# ECG.net
KiCad netlist of a schematic drawn in EAGLE
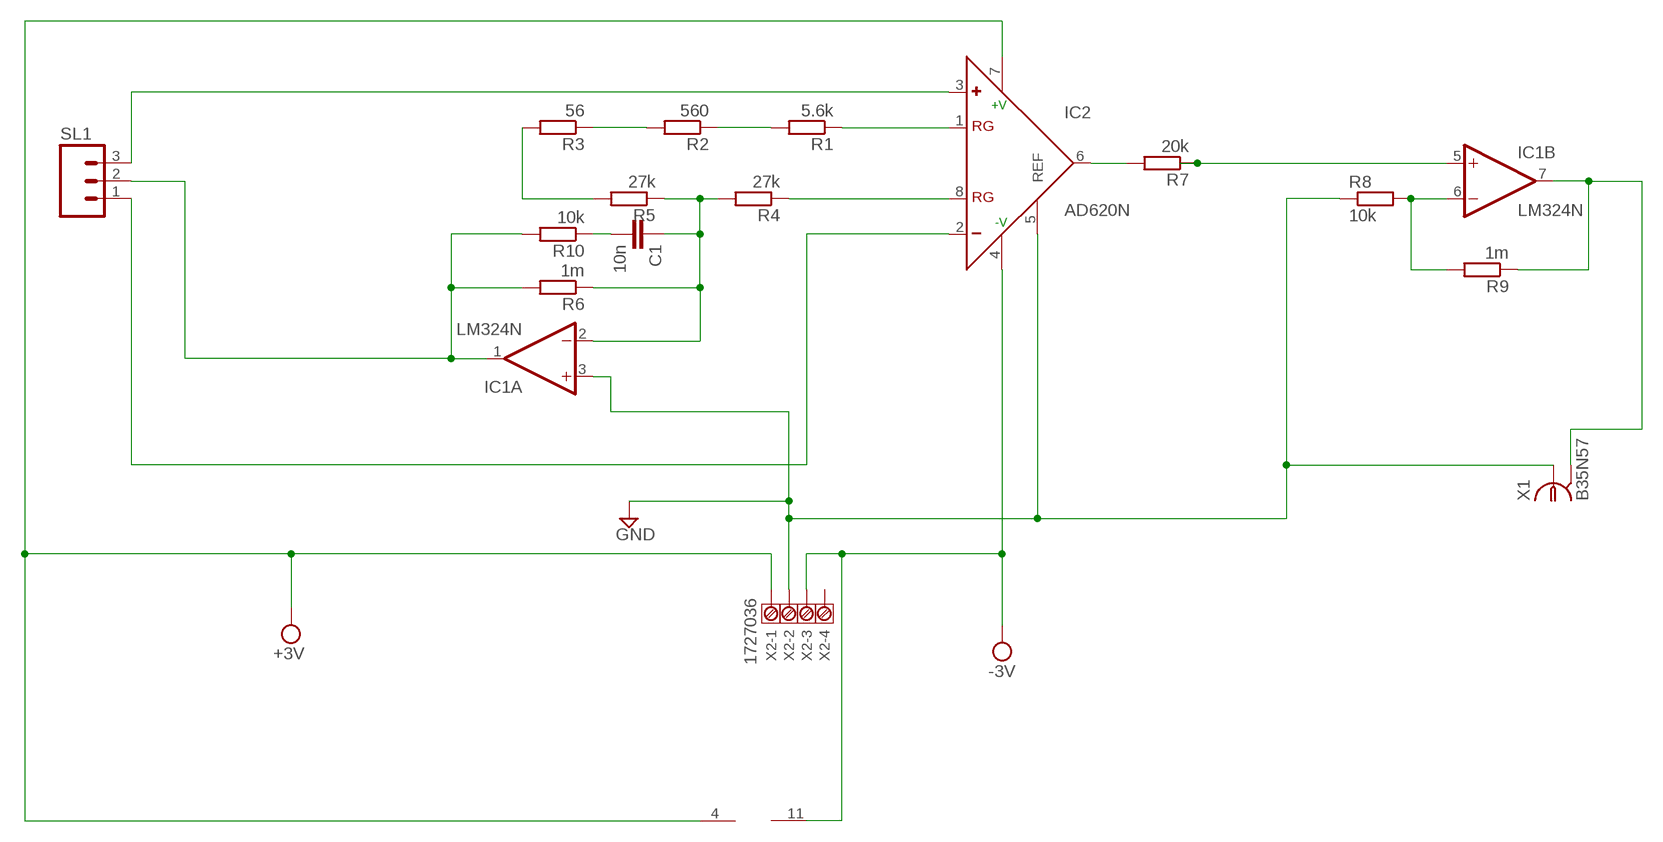
[diagram p0: schematic, sheet 1]

(export (version "E")
  (design (tool "Eeschema 10.0.6"))
  (components
    (comp (ref "C1")
      (value "10n")
      (footprint "eagle-import:C025-024X044")
      (libsource (lib "eagle-import") (part "C-EU025-024X044"))
    )
    (comp (ref "IC1")
      (value "LM324N")
      (footprint "eagle-import:DIL14")
      (libsource (lib "eagle-import") (part "LM324N"))
    )
    (comp (ref "IC2")
      (value "AD620N")
      (footprint "eagle-import:DIL08")
      (fields (field (name "MF") "ALTERA CORPORATION") (field (name "MPN") "AD620AN"))
      (libsource (lib "eagle-import") (part "AD620N"))
    )
    (comp (ref "R1")
      (value "5.6k")
      (footprint "eagle-import:0204_7")
      (libsource (lib "eagle-import") (part "R-EU_0204/7"))
    )
    (comp (ref "R2")
      (value "560")
      (footprint "eagle-import:0204_7")
      (libsource (lib "eagle-import") (part "R-EU_0204/7"))
    )
    (comp (ref "R3")
      (value "56")
      (footprint "eagle-import:0204_7")
      (libsource (lib "eagle-import") (part "R-EU_0204/7"))
    )
    (comp (ref "R4")
      (value "27k")
      (footprint "eagle-import:0204_7")
      (libsource (lib "eagle-import") (part "R-EU_0204/7"))
    )
    (comp (ref "R5")
      (value "27k")
      (footprint "eagle-import:0204_7")
      (libsource (lib "eagle-import") (part "R-EU_0204/7"))
    )
    (comp (ref "R6")
      (value "1m")
      (footprint "eagle-import:0204_7")
      (libsource (lib "eagle-import") (part "R-EU_0204/7"))
    )
    (comp (ref "R7")
      (value "20k")
      (footprint "eagle-import:0204_7")
      (libsource (lib "eagle-import") (part "R-EU_0204/7"))
    )
    (comp (ref "R8")
      (value "10k")
      (footprint "eagle-import:0204_7")
      (libsource (lib "eagle-import") (part "R-EU_0204/7"))
    )
    (comp (ref "R9")
      (value "1m")
      (footprint "eagle-import:0204_7")
      (libsource (lib "eagle-import") (part "R-EU_0204/7"))
    )
    (comp (ref "R10")
      (value "10k")
      (footprint "eagle-import:0204_7")
      (libsource (lib "eagle-import") (part "R-EU_0204/7"))
    )
    (comp (ref "SL1")
      (value "MA03")
      (footprint "eagle-import:03P")
      (libsource (lib "eagle-import") (part "MA03"))
    )
    (comp (ref "X1")
      (value "B35N57")
      (footprint "eagle-import:B35N57")
      (libsource (lib "eagle-import") (part "B35N57"))
    )
    (comp (ref "X2")
      (value "1727036")
      (footprint "eagle-import:1727036")
      (fields (field (name "MF") "FARNELL"))
      (libsource (lib "eagle-import") (part "1727036"))
    )
  )
  (nets
    (net (code "1") (name "+3V") (class "Default")
      (node (ref "IC1") (pin "4") (pinfunction "V+_4") (pintype "power_in"))
      (node (ref "IC2") (pin "7") (pinfunction "+V_7") (pintype "power_in"))
      (node (ref "X2") (pin "1") (pinfunction "1_1") (pintype "passive"))
    )
    (net (code "2") (name "-3V") (class "Default")
      (node (ref "IC1") (pin "11") (pinfunction "V-_11") (pintype "power_in"))
      (node (ref "IC2") (pin "4") (pinfunction "-V_4") (pintype "power_in"))
      (node (ref "X2") (pin "3") (pinfunction "1_3") (pintype "passive"))
    )
    (net (code "3") (name "GND") (class "Default")
      (node (ref "IC1") (pin "3") (pinfunction "+IN_3") (pintype "input"))
      (node (ref "IC2") (pin "5") (pinfunction "REF_5") (pintype "passive"))
      (node (ref "R8") (pin "1") (pinfunction "1_1") (pintype "passive"))
      (node (ref "X1") (pin "1") (pinfunction "1_1") (pintype "passive"))
      (node (ref "X2") (pin "2") (pinfunction "1_2") (pintype "passive"))
    )
    (net (code "4") (name "Net-(C1-Pad2)") (class "Default")
      (node (ref "C1") (pin "2") (pinfunction "2_2") (pintype "passive"))
      (node (ref "R10") (pin "1") (pinfunction "1_1") (pintype "passive"))
    )
    (net (code "5") (name "Net-(IC1A--IN)") (class "Default")
      (node (ref "C1") (pin "1") (pinfunction "1_1") (pintype "passive"))
      (node (ref "IC1") (pin "2") (pinfunction "-IN_2") (pintype "input"))
      (node (ref "R4") (pin "2") (pinfunction "2_2") (pintype "passive"))
      (node (ref "R5") (pin "1") (pinfunction "1_1") (pintype "passive"))
      (node (ref "R6") (pin "1") (pinfunction "1_1") (pintype "passive"))
    )
    (net (code "6") (name "Net-(IC1A-OUT)") (class "Default")
      (node (ref "IC1") (pin "1") (pinfunction "OUT_1") (pintype "output"))
      (node (ref "R10") (pin "2") (pinfunction "2_2") (pintype "passive"))
      (node (ref "R6") (pin "2") (pinfunction "2_2") (pintype "passive"))
      (node (ref "SL1") (pin "2") (pinfunction "2_2") (pintype "passive"))
    )
    (net (code "7") (name "Net-(IC1B-+IN)") (class "Default")
      (node (ref "IC1") (pin "5") (pinfunction "+IN_5") (pintype "input"))
      (node (ref "R7") (pin "1") (pinfunction "1_1") (pintype "passive"))
    )
    (net (code "8") (name "Net-(IC1B--IN)") (class "Default")
      (node (ref "IC1") (pin "6") (pinfunction "-IN_6") (pintype "input"))
      (node (ref "R8") (pin "2") (pinfunction "2_2") (pintype "passive"))
      (node (ref "R9") (pin "2") (pinfunction "2_2") (pintype "passive"))
    )
    (net (code "9") (name "Net-(IC1B-OUT)") (class "Default")
      (node (ref "IC1") (pin "7") (pinfunction "OUT_7") (pintype "output"))
      (node (ref "R9") (pin "1") (pinfunction "1_1") (pintype "passive"))
      (node (ref "X1") (pin "2") (pinfunction "2_2") (pintype "passive"))
      (node (ref "X1") (pin "3") (pinfunction "2_3") (pintype "passive"))
      (node (ref "X1") (pin "4") (pinfunction "2_4") (pintype "passive"))
      (node (ref "X1") (pin "5") (pinfunction "2_5") (pintype "passive"))
    )
    (net (code "10") (name "Net-(IC2-+)") (class "Default")
      (node (ref "IC2") (pin "3") (pinfunction "+_3") (pintype "input"))
      (node (ref "SL1") (pin "3") (pinfunction "3_3") (pintype "passive"))
    )
    (net (code "11") (name "Net-(IC2--)") (class "Default")
      (node (ref "IC2") (pin "2") (pinfunction "-_2") (pintype "input"))
      (node (ref "SL1") (pin "1") (pinfunction "1_1") (pintype "passive"))
    )
    (net (code "12") (name "Net-(IC2-OUT)") (class "Default")
      (node (ref "IC2") (pin "6") (pinfunction "OUT_6") (pintype "output"))
      (node (ref "R7") (pin "2") (pinfunction "2_2") (pintype "passive"))
    )
    (net (code "13") (name "Net-(IC2-RG-Pad1)") (class "Default")
      (node (ref "IC2") (pin "1") (pinfunction "RG_1") (pintype "passive"))
      (node (ref "R1") (pin "1") (pinfunction "1_1") (pintype "passive"))
    )
    (net (code "14") (name "Net-(IC2-RG-Pad8)") (class "Default")
      (node (ref "IC2") (pin "8") (pinfunction "RG_8") (pintype "passive"))
      (node (ref "R4") (pin "1") (pinfunction "1_1") (pintype "passive"))
    )
    (net (code "15") (name "Net-(R1-Pad2)") (class "Default")
      (node (ref "R1") (pin "2") (pinfunction "2_2") (pintype "passive"))
      (node (ref "R2") (pin "1") (pinfunction "1_1") (pintype "passive"))
    )
    (net (code "16") (name "Net-(R2-Pad2)") (class "Default")
      (node (ref "R2") (pin "2") (pinfunction "2_2") (pintype "passive"))
      (node (ref "R3") (pin "1") (pinfunction "1_1") (pintype "passive"))
    )
    (net (code "17") (name "Net-(R3-Pad2)") (class "Default")
      (node (ref "R3") (pin "2") (pinfunction "2_2") (pintype "passive"))
      (node (ref "R5") (pin "2") (pinfunction "2_2") (pintype "passive"))
    )
    (net (code "18") (name "unconnected-(X2D-1-Pad4)") (class "Default")
      (node (ref "X2") (pin "4") (pinfunction "1_4") (pintype "passive"))
    )
  )
)
